# HapticVibrationShield_v2.net
KiCad netlist of a schematic drawn in EAGLE
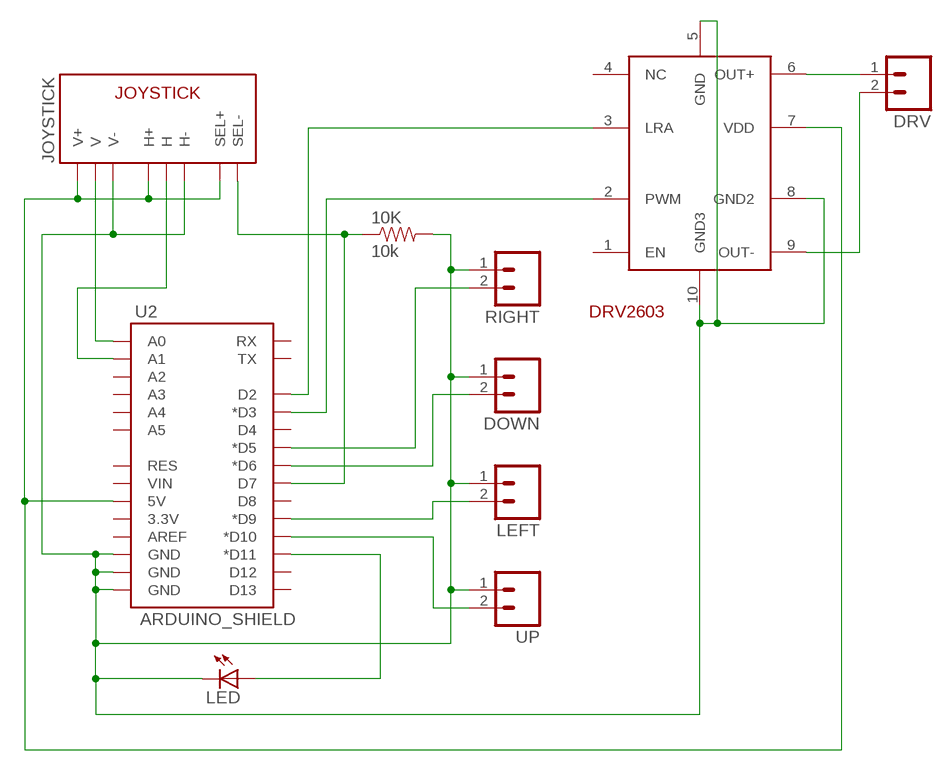
[diagram p0: schematic, sheet 1]

(export (version "E")
  (design (tool "Eeschema 10.0.6"))
  (components
    (comp (ref "10K")
      (value "10k")
      (footprint "eagle-import:R2010")
      (libsource (lib "eagle-import") (part "RESISTOR2010"))
    )
    (comp (ref "DOWN")
      (value "M02LOCK_LONGPADS")
      (footprint "eagle-import:1X02_LOCK_LONGPADS")
      (libsource (lib "eagle-import") (part "M02LOCK_LONGPADS"))
    )
    (comp (ref "DRV")
      (value "M02LOCK_LONGPADS")
      (footprint "eagle-import:1X02_LOCK_LONGPADS")
      (libsource (lib "eagle-import") (part "M02LOCK_LONGPADS"))
    )
    (comp (ref "DRV2603")
      (value "QFN-10QFN-10")
      (footprint "eagle-import:QFN-10")
      (libsource (lib "eagle-import") (part "QFN-10QFN-10"))
    )
    (comp (ref "JOYSTICK")
      (value "JOYSTICKPTH")
      (footprint "eagle-import:JOYSTICK")
      (libsource (lib "eagle-import") (part "JOYSTICKPTH"))
    )
    (comp (ref "LED")
      (value "LED5MM")
      (footprint "eagle-import:LED5MM")
      (libsource (lib "eagle-import") (part "LED5MM"))
    )
    (comp (ref "LEFT")
      (value "M02LOCK_LONGPADS")
      (footprint "eagle-import:1X02_LOCK_LONGPADS")
      (libsource (lib "eagle-import") (part "M02LOCK_LONGPADS"))
    )
    (comp (ref "RIGHT")
      (value "M02LOCK_LONGPADS")
      (footprint "eagle-import:1X02_LOCK_LONGPADS")
      (libsource (lib "eagle-import") (part "M02LOCK_LONGPADS"))
    )
    (comp (ref "U2")
      (value "ARDUINO_SHIELD")
      (footprint "eagle-import:DUEMILANOVE_SHIELD")
      (libsource (lib "eagle-import") (part "ARDUINO_SHIELDLABEL"))
    )
    (comp (ref "UP")
      (value "M02LOCK_LONGPADS")
      (footprint "eagle-import:1X02_LOCK_LONGPADS")
      (libsource (lib "eagle-import") (part "M02LOCK_LONGPADS"))
    )
  )
  (nets
    (net (code "1") (name "Net-(DRV2603-GND)") (class "Default")
      (node (ref "10K") (pin "2") (pinfunction "2_2") (pintype "passive"))
      (node (ref "DOWN") (pin "1") (pinfunction "1_1") (pintype "passive"))
      (node (ref "DRV2603") (pin "10") (pinfunction "GND3_10") (pintype "bidirectional"))
      (node (ref "DRV2603") (pin "5") (pinfunction "GND_5") (pintype "bidirectional"))
      (node (ref "DRV2603") (pin "8") (pinfunction "GND2_8") (pintype "bidirectional"))
      (node (ref "JOYSTICK") (pin "H3") (pinfunction "H-_H3") (pintype "bidirectional"))
      (node (ref "JOYSTICK") (pin "V3") (pinfunction "V-_V3") (pintype "bidirectional"))
      (node (ref "LED") (pin "K") (pinfunction "C_K") (pintype "passive"))
      (node (ref "LEFT") (pin "1") (pinfunction "1_1") (pintype "passive"))
      (node (ref "RIGHT") (pin "1") (pinfunction "1_1") (pintype "passive"))
      (node (ref "U2") (pin "GND@0") (pinfunction "GND_GND@0") (pintype "bidirectional"))
      (node (ref "U2") (pin "GND@1") (pinfunction "GND_GND@1") (pintype "bidirectional"))
      (node (ref "U2") (pin "GND@2") (pinfunction "GND_GND@2") (pintype "bidirectional"))
      (node (ref "UP") (pin "1") (pinfunction "1_1") (pintype "passive"))
    )
    (net (code "2") (name "Net-(DRV2603-LRA)") (class "Default")
      (node (ref "DRV2603") (pin "3") (pinfunction "LRA_3") (pintype "bidirectional"))
      (node (ref "U2") (pin "D2") (pinfunction "D2_D2") (pintype "bidirectional"))
    )
    (net (code "3") (name "Net-(DRV2603-OUT+)") (class "Default")
      (node (ref "DRV") (pin "1") (pinfunction "1_1") (pintype "passive"))
      (node (ref "DRV2603") (pin "6") (pinfunction "OUT+_6") (pintype "bidirectional"))
    )
    (net (code "4") (name "Net-(DRV2603-OUT-)") (class "Default")
      (node (ref "DRV") (pin "2") (pinfunction "2_2") (pintype "passive"))
      (node (ref "DRV2603") (pin "9") (pinfunction "OUT-_9") (pintype "bidirectional"))
    )
    (net (code "5") (name "Net-(DRV2603-PWM)") (class "Default")
      (node (ref "DRV2603") (pin "2") (pinfunction "PWM_2") (pintype "bidirectional"))
      (node (ref "U2") (pin "D3") (pinfunction "*D3_D3") (pintype "bidirectional"))
    )
    (net (code "6") (name "Net-(DRV2603-VDD)") (class "Default")
      (node (ref "DRV2603") (pin "7") (pinfunction "VDD_7") (pintype "bidirectional"))
      (node (ref "JOYSTICK") (pin "B1A") (pinfunction "SEL+_B1A") (pintype "bidirectional"))
      (node (ref "JOYSTICK") (pin "H1") (pinfunction "H+_H1") (pintype "bidirectional"))
      (node (ref "JOYSTICK") (pin "V1") (pinfunction "V+_V1") (pintype "bidirectional"))
      (node (ref "U2") (pin "5V") (pinfunction "5V_5V") (pintype "bidirectional"))
    )
    (net (code "7") (name "Net-(JOYSTICK-H)") (class "Default")
      (node (ref "JOYSTICK") (pin "H2") (pinfunction "H_H2") (pintype "bidirectional"))
      (node (ref "U2") (pin "A1") (pinfunction "A1_A1") (pintype "bidirectional"))
    )
    (net (code "8") (name "Net-(JOYSTICK-SEL-)") (class "Default")
      (node (ref "10K") (pin "1") (pinfunction "1_1") (pintype "passive"))
      (node (ref "JOYSTICK") (pin "B2A") (pinfunction "SEL-_B2A") (pintype "bidirectional"))
      (node (ref "U2") (pin "D7") (pinfunction "D7_D7") (pintype "bidirectional"))
    )
    (net (code "9") (name "Net-(JOYSTICK-V)") (class "Default")
      (node (ref "JOYSTICK") (pin "V2") (pinfunction "V_V2") (pintype "bidirectional"))
      (node (ref "U2") (pin "A0") (pinfunction "A0_A0") (pintype "bidirectional"))
    )
    (net (code "10") (name "Net-(U2-*D5)") (class "Default")
      (node (ref "RIGHT") (pin "2") (pinfunction "2_2") (pintype "passive"))
      (node (ref "U2") (pin "D5") (pinfunction "*D5_D5") (pintype "bidirectional"))
    )
    (net (code "11") (name "Net-(U2-*D6)") (class "Default")
      (node (ref "DOWN") (pin "2") (pinfunction "2_2") (pintype "passive"))
      (node (ref "U2") (pin "D6") (pinfunction "*D6_D6") (pintype "bidirectional"))
    )
    (net (code "12") (name "Net-(U2-*D9)") (class "Default")
      (node (ref "LEFT") (pin "2") (pinfunction "2_2") (pintype "passive"))
      (node (ref "U2") (pin "D9") (pinfunction "*D9_D9") (pintype "bidirectional"))
    )
    (net (code "13") (name "Net-(U2-*D10)") (class "Default")
      (node (ref "U2") (pin "D10") (pinfunction "*D10_D10") (pintype "bidirectional"))
      (node (ref "UP") (pin "2") (pinfunction "2_2") (pintype "passive"))
    )
    (net (code "14") (name "Net-(U2-*D11)") (class "Default")
      (node (ref "LED") (pin "A") (pinfunction "A_A") (pintype "passive"))
      (node (ref "U2") (pin "D11") (pinfunction "*D11_D11") (pintype "bidirectional"))
    )
    (net (code "15") (name "unconnected-(DRV2603-EN-Pad1)") (class "Default")
      (node (ref "DRV2603") (pin "1") (pinfunction "EN_1") (pintype "bidirectional"))
    )
    (net (code "16") (name "unconnected-(DRV2603-NC-Pad4)") (class "Default")
      (node (ref "DRV2603") (pin "4") (pinfunction "NC_4") (pintype "bidirectional"))
    )
    (net (code "17") (name "unconnected-(U2-Pad3.3V)") (class "Default")
      (node (ref "U2") (pin "3.3V") (pinfunction "3.3V_3.3V") (pintype "bidirectional"))
    )
    (net (code "18") (name "unconnected-(U2-PadA2)") (class "Default")
      (node (ref "U2") (pin "A2") (pinfunction "A2_A2") (pintype "bidirectional"))
    )
    (net (code "19") (name "unconnected-(U2-PadA3)") (class "Default")
      (node (ref "U2") (pin "A3") (pinfunction "A3_A3") (pintype "bidirectional"))
    )
    (net (code "20") (name "unconnected-(U2-PadA4)") (class "Default")
      (node (ref "U2") (pin "A4") (pinfunction "A4_A4") (pintype "bidirectional"))
    )
    (net (code "21") (name "unconnected-(U2-PadA5)") (class "Default")
      (node (ref "U2") (pin "A5") (pinfunction "A5_A5") (pintype "bidirectional"))
    )
    (net (code "22") (name "unconnected-(U2-PadAREF)") (class "Default")
      (node (ref "U2") (pin "AREF") (pinfunction "AREF_AREF") (pintype "bidirectional"))
    )
    (net (code "23") (name "unconnected-(U2-PadD4)") (class "Default")
      (node (ref "U2") (pin "D4") (pinfunction "D4_D4") (pintype "bidirectional"))
    )
    (net (code "24") (name "unconnected-(U2-PadD8)") (class "Default")
      (node (ref "U2") (pin "D8") (pinfunction "D8_D8") (pintype "bidirectional"))
    )
    (net (code "25") (name "unconnected-(U2-PadD12)") (class "Default")
      (node (ref "U2") (pin "D12") (pinfunction "D12_D12") (pintype "bidirectional"))
    )
    (net (code "26") (name "unconnected-(U2-PadD13)") (class "Default")
      (node (ref "U2") (pin "D13") (pinfunction "D13_D13") (pintype "bidirectional"))
    )
    (net (code "27") (name "unconnected-(U2-PadRES)") (class "Default")
      (node (ref "U2") (pin "RES") (pinfunction "RES_RES") (pintype "bidirectional"))
    )
    (net (code "28") (name "unconnected-(U2-PadRX)") (class "Default")
      (node (ref "U2") (pin "RX") (pinfunction "RX_RX") (pintype "bidirectional"))
    )
    (net (code "29") (name "unconnected-(U2-PadTX)") (class "Default")
      (node (ref "U2") (pin "TX") (pinfunction "TX_TX") (pintype "bidirectional"))
    )
    (net (code "30") (name "unconnected-(U2-PadVIN)") (class "Default")
      (node (ref "U2") (pin "VIN") (pinfunction "VIN_VIN") (pintype "bidirectional"))
    )
  )
)
